# ReboostV2_USB.net
KiCad netlist of a schematic drawn in Altium Designer
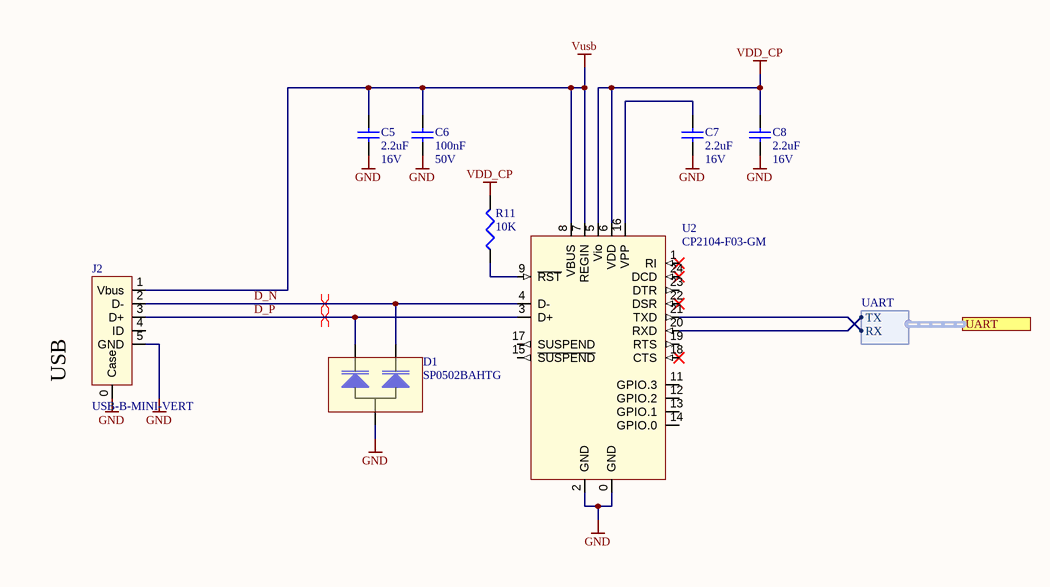
[diagram p0: ReboostV2_USB.SchDoc]

(export (version "E")
  (design (tool "Eeschema 10.0.6"))
  (components
    (comp (ref "C5")
      (value "2.2uF")
      (footprint "C0603")
      (description "Capacitor, 2.2uF, 16V, X5R")
      (fields
        (field (name "VOLTAGE RATING") "16V")
        (field (name "MANUFACTURER") "MURATA")
        (field (name "MANUFACTURER PART NUMBER") "GRM188R61C225KE15D")
      )
      (libsource (lib "Reboostv2") (part "2.2uF/0603/CER/16V"))
    )
    (comp (ref "C6")
      (value "100nF")
      (footprint "C0603")
      (description "Capacitor, 100nF, 50V, X7R")
      (fields
        (field (name "VOLTAGE RATING") "50V")
        (field (name "MANUFACTURER") "MULTICOMP")
        (field (name "MANUFACTURER PART NUMBER") "MCCA000255")
      )
      (libsource (lib "Reboostv2") (part "100nF/0603/CER/50V"))
    )
    (comp (ref "C7")
      (value "2.2uF")
      (footprint "C0603")
      (description "Capacitor, 2.2uF, 16V, X5R")
      (fields
        (field (name "VOLTAGE RATING") "16V")
        (field (name "MANUFACTURER") "MURATA")
        (field (name "MANUFACTURER PART NUMBER") "GRM188R61C225KE15D")
      )
      (libsource (lib "Reboostv2") (part "2.2uF/0603/CER/16V"))
    )
    (comp (ref "C8")
      (value "2.2uF")
      (footprint "C0603")
      (description "Capacitor, 2.2uF, 16V, X5R")
      (fields
        (field (name "VOLTAGE RATING") "16V")
        (field (name "MANUFACTURER") "MURATA")
        (field (name "MANUFACTURER PART NUMBER") "GRM188R61C225KE15D")
      )
      (libsource (lib "Reboostv2") (part "2.2uF/0603/CER/16V"))
    )
    (comp (ref "D1")
      (value "SP0502BAHTG")
      (footprint "SOT23")
      (description "Diode TVS Dual, Vrwm: 5.5V Vc: 8V")
      (fields (field (name "MANUFACTURER") "LITTLEFUSE"))
      (libsource (lib "Reboostv2") (part "SP0502BAHTG"))
    )
    (comp (ref "J2")
      (value "USB-B-MINI-VERT")
      (footprint "USB-B-MINI-VERT")
      (description "Connector, Usb B Mini, Vertical, TH, WR-COM")
      (fields (field (name "MANUFACTURER") "Wurth Elektronik") (field (name "MPN") "651005136421"))
      (libsource (lib "Reboostv2") (part "WE-651005136421"))
    )
    (comp (ref "R11")
      (value "10K")
      (footprint "0603")
      (description "Resistor, 10K, 1%, 0.063W, 50V, 100PPM, 0603")
      (fields
        (field (name "MANUFACTURER") "VISHAY DRALORIC")
        (field (name "MANUFACTURER PART NUMBER") "CRCW060310K0FKEA")
      )
      (libsource (lib "Reboostv2") (part "10K/0603/0063W/50V"))
    )
    (comp (ref "U2")
      (value "CP2104-F03-GM")
      (footprint "QFN24")
      (description "USB to UART converter")
      (fields (field (name "MANUFACTURER") "Silicon Labs"))
      (libsource (lib "Reboostv2") (part "CP2104-F03-GM"))
    )
  )
  (nets
    (net (code "2") (name "/D_N") (class "Default")
      (node (ref "D1") (pin "K1") (pinfunction "K1_K1") (pintype "passive"))
      (node (ref "J2") (pin "2") (pinfunction "D-_2") (pintype "passive"))
      (node (ref "U2") (pin "4") (pinfunction "D-_4") (pintype "bidirectional"))
    )
    (net (code "3") (name "/D_P") (class "Default")
      (node (ref "D1") (pin "K2") (pinfunction "K2_K2") (pintype "passive"))
      (node (ref "J2") (pin "3") (pinfunction "D+_3") (pintype "passive"))
      (node (ref "U2") (pin "3") (pinfunction "D+_3") (pintype "bidirectional"))
    )
    (net (code "4") (name "/RX") (class "Default")
      (node (ref "U2") (pin "21") (pinfunction "TXD_21") (pintype "output"))
    )
    (net (code "5") (name "/TX") (class "Default")
      (node (ref "U2") (pin "20") (pinfunction "RXD_20") (pintype "input"))
    )
    (net (code "7") (name "GND") (class "Default")
      (node (ref "C5") (pin "1") (pinfunction "1_1") (pintype "passive"))
      (node (ref "C6") (pin "1") (pinfunction "1_1") (pintype "passive"))
      (node (ref "C7") (pin "1") (pinfunction "1_1") (pintype "passive"))
      (node (ref "C8") (pin "1") (pinfunction "1_1") (pintype "passive"))
      (node (ref "D1") (pin "A") (pinfunction "A_A") (pintype "passive"))
      (node (ref "J2") (pin "0") (pinfunction "Case_0") (pintype "passive"))
      (node (ref "J2") (pin "5") (pinfunction "GND_5") (pintype "passive"))
      (node (ref "U2") (pin "0") (pinfunction "GND_0") (pintype "power_in"))
      (node (ref "U2") (pin "2") (pinfunction "GND_2") (pintype "power_in"))
    )
    (net (code "8") (name "Net-(U2-VPP)") (class "Default")
      (node (ref "C7") (pin "2") (pinfunction "2_2") (pintype "passive"))
      (node (ref "U2") (pin "16") (pinfunction "VPP_16") (pintype "power_in"))
    )
    (net (code "9") (name "Net-(U2-~{RST})") (class "Default")
      (node (ref "R11") (pin "1") (pinfunction "1_1") (pintype "passive"))
      (node (ref "U2") (pin "9") (pinfunction "~{RST}_9") (pintype "input"))
    )
    (net (code "10") (name "VDD_CP") (class "Default")
      (node (ref "C8") (pin "2") (pinfunction "2_2") (pintype "passive"))
      (node (ref "R11") (pin "2") (pinfunction "2_2") (pintype "passive"))
      (node (ref "U2") (pin "5") (pinfunction "Vio_5") (pintype "passive"))
      (node (ref "U2") (pin "6") (pinfunction "VDD_6") (pintype "power_in"))
    )
    (net (code "11") (name "Vusb") (class "Default")
      (node (ref "C5") (pin "2") (pinfunction "2_2") (pintype "passive"))
      (node (ref "C6") (pin "2") (pinfunction "2_2") (pintype "passive"))
      (node (ref "J2") (pin "1") (pinfunction "Vbus_1") (pintype "passive"))
      (node (ref "U2") (pin "7") (pinfunction "REGIN_7") (pintype "power_in"))
      (node (ref "U2") (pin "8") (pinfunction "VBUS_8") (pintype "power_in"))
    )
    (net (code "12") (name "unconnected-(J2-ID-Pad4)") (class "Default")
      (node (ref "J2") (pin "4") (pinfunction "ID_4") (pintype "passive"))
    )
    (net (code "13") (name "unconnected-(U2-CTS-Pad18)") (class "Default")
      (node (ref "U2") (pin "18") (pinfunction "CTS_18") (pintype "input+no_connect"))
    )
    (net (code "14") (name "unconnected-(U2-DCD-Pad24)") (class "Default")
      (node (ref "U2") (pin "24") (pinfunction "DCD_24") (pintype "input+no_connect"))
    )
    (net (code "15") (name "unconnected-(U2-DSR-Pad22)") (class "Default")
      (node (ref "U2") (pin "22") (pinfunction "DSR_22") (pintype "input+no_connect"))
    )
    (net (code "16") (name "unconnected-(U2-DTR-Pad23)") (class "Default")
      (node (ref "U2") (pin "23") (pinfunction "DTR_23") (pintype "output"))
    )
    (net (code "17") (name "unconnected-(U2-GPIO.0-Pad14)") (class "Default")
      (node (ref "U2") (pin "14") (pinfunction "GPIO.0_14") (pintype "passive"))
    )
    (net (code "18") (name "unconnected-(U2-GPIO.1-Pad13)") (class "Default")
      (node (ref "U2") (pin "13") (pinfunction "GPIO.1_13") (pintype "passive"))
    )
    (net (code "19") (name "unconnected-(U2-GPIO.2-Pad12)") (class "Default")
      (node (ref "U2") (pin "12") (pinfunction "GPIO.2_12") (pintype "passive"))
    )
    (net (code "20") (name "unconnected-(U2-GPIO.3-Pad11)") (class "Default")
      (node (ref "U2") (pin "11") (pinfunction "GPIO.3_11") (pintype "passive"))
    )
    (net (code "21") (name "unconnected-(U2-RI-Pad1)") (class "Default")
      (node (ref "U2") (pin "1") (pinfunction "RI_1") (pintype "input+no_connect"))
    )
    (net (code "22") (name "unconnected-(U2-RTS-Pad19)") (class "Default")
      (node (ref "U2") (pin "19") (pinfunction "RTS_19") (pintype "output"))
    )
    (net (code "23") (name "unconnected-(U2-SUSPEND-Pad17)") (class "Default")
      (node (ref "U2") (pin "17") (pinfunction "SUSPEND_17") (pintype "output"))
    )
    (net (code "24") (name "unconnected-(U2-~{SUSPEND}-Pad15)") (class "Default")
      (node (ref "U2") (pin "15") (pinfunction "~{SUSPEND}_15") (pintype "output"))
    )
  )
)
